# ATMEGA128RF.net
KiCad netlist of a schematic drawn in Altium Designer
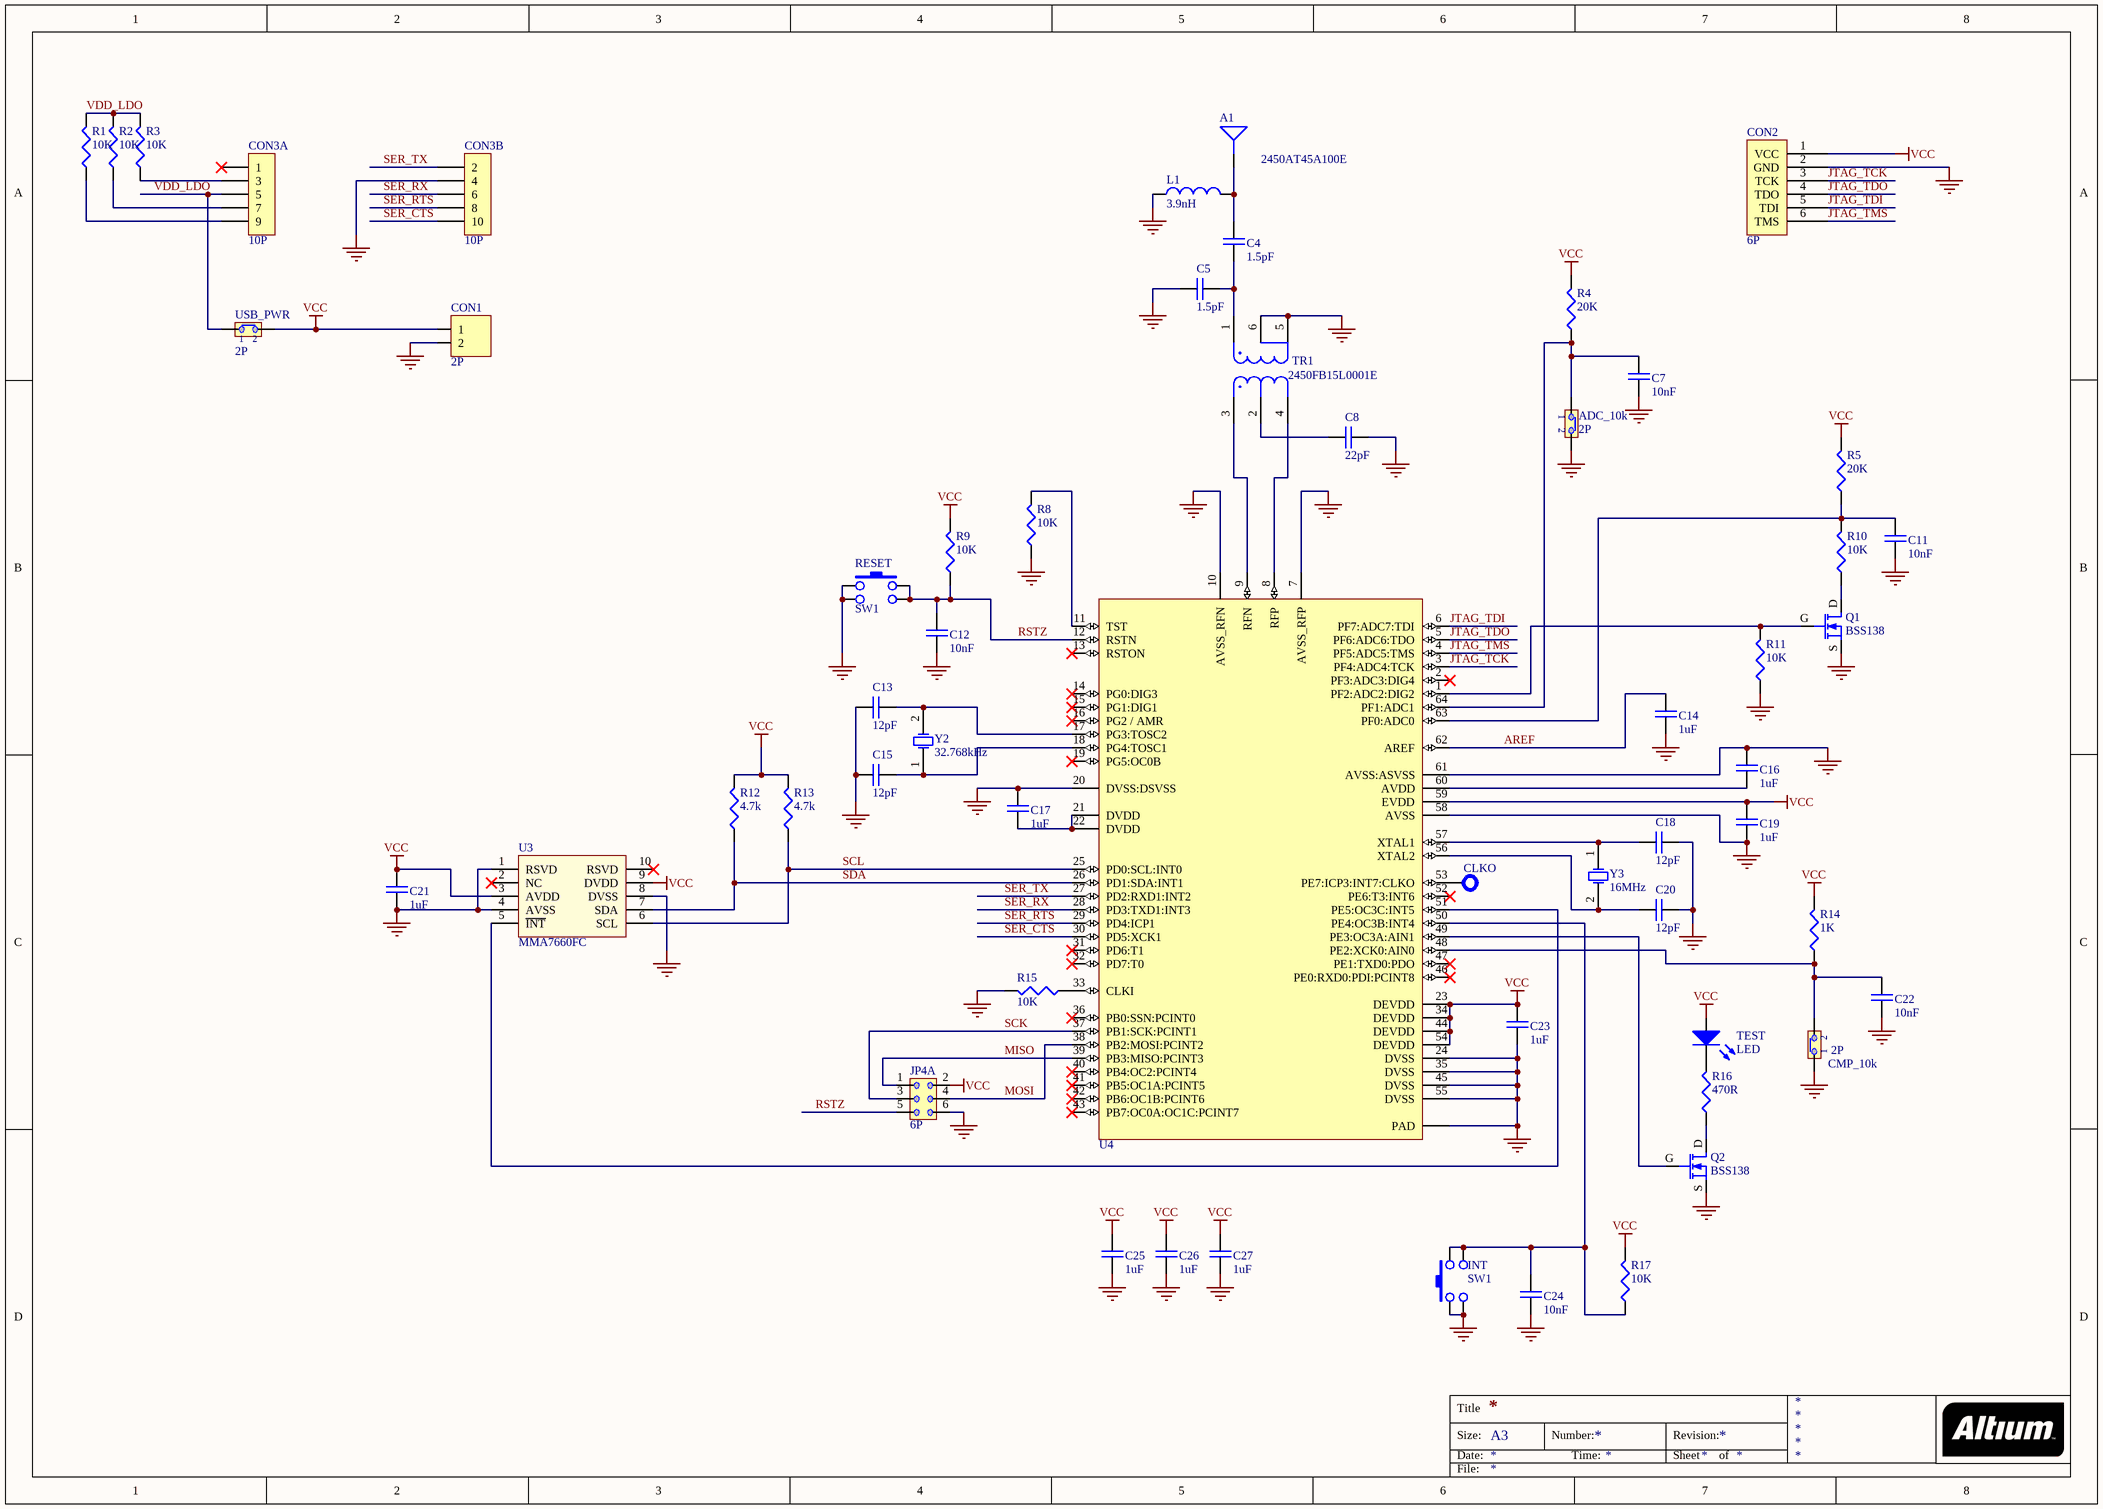
[diagram p0: ATMEGA128RF.SchDoc]

(export (version "E")
  (design (tool "Eeschema 10.0.6"))
  (components
    (comp (ref "A1")
      (value "2450AT45A100E")
      (footprint "2450AT45A100E")
      (description "ANTENNA")
      (libsource (lib "Alcetronics_Devices") (part "Antenna SE"))
    )
    (comp (ref "ADC_10k")
      (value "2P")
      (footprint "SIP-2")
      (description "2-pin Jumper")
      (fields (field (name "OWNER") "Nuno Brum"))
      (libsource (lib "Alcetronics_EM") (part "JMP2"))
    )
    (comp (ref "C4")
      (value "1.5pF")
      (footprint "0402")
      (description "Capacitor")
      (fields (field (name "OWNER") "Nuno Brum"))
      (libsource (lib "Alcetronics_Devices") (part "CAP"))
    )
    (comp (ref "C5")
      (value "1.5pF")
      (footprint "0402")
      (description "Capacitor")
      (fields (field (name "OWNER") "Nuno Brum"))
      (libsource (lib "Alcetronics_Devices") (part "CAP"))
    )
    (comp (ref "C7")
      (value "10nF")
      (footprint "0603")
      (description "Capacitor")
      (fields (field (name "OWNER") "Nuno Brum"))
      (libsource (lib "Alcetronics_Devices") (part "CAP"))
    )
    (comp (ref "C8")
      (value "22pF")
      (footprint "0402")
      (description "Capacitor")
      (fields (field (name "OWNER") "Nuno Brum"))
      (libsource (lib "Alcetronics_Devices") (part "CAP"))
    )
    (comp (ref "C11")
      (value "10nF")
      (footprint "0603")
      (description "Capacitor")
      (fields (field (name "OWNER") "Nuno Brum"))
      (libsource (lib "Alcetronics_Devices") (part "CAP"))
    )
    (comp (ref "C12")
      (value "10nF")
      (footprint "0603")
      (description "Capacitor")
      (fields (field (name "OWNER") "Nuno Brum"))
      (libsource (lib "Alcetronics_Devices") (part "CAP"))
    )
    (comp (ref "C13")
      (value "12pF")
      (footprint "0603")
      (description "Capacitor")
      (fields (field (name "OWNER") "Nuno Brum"))
      (libsource (lib "Alcetronics_Devices") (part "CAP"))
    )
    (comp (ref "C14")
      (value "1uF")
      (footprint "0603")
      (description "Capacitor")
      (fields (field (name "OWNER") "Nuno Brum"))
      (libsource (lib "Alcetronics_Devices") (part "CAP"))
    )
    (comp (ref "C15")
      (value "12pF")
      (footprint "0603")
      (description "Capacitor")
      (fields (field (name "OWNER") "Nuno Brum"))
      (libsource (lib "Alcetronics_Devices") (part "CAP"))
    )
    (comp (ref "C16")
      (value "1uF")
      (footprint "0603")
      (description "Capacitor")
      (fields (field (name "OWNER") "Nuno Brum"))
      (libsource (lib "Alcetronics_Devices") (part "CAP"))
    )
    (comp (ref "C17")
      (value "1uF")
      (footprint "0603")
      (description "Capacitor")
      (fields (field (name "OWNER") "Nuno Brum"))
      (libsource (lib "Alcetronics_Devices") (part "CAP"))
    )
    (comp (ref "C18")
      (value "12pF")
      (footprint "0603")
      (description "Capacitor")
      (fields (field (name "OWNER") "Nuno Brum"))
      (libsource (lib "Alcetronics_Devices") (part "CAP"))
    )
    (comp (ref "C19")
      (value "1uF")
      (footprint "0603")
      (description "Capacitor")
      (fields (field (name "OWNER") "Nuno Brum"))
      (libsource (lib "Alcetronics_Devices") (part "CAP"))
    )
    (comp (ref "C20")
      (value "12pF")
      (footprint "0603")
      (description "Capacitor")
      (fields (field (name "OWNER") "Nuno Brum"))
      (libsource (lib "Alcetronics_Devices") (part "CAP"))
    )
    (comp (ref "C21")
      (value "1uF")
      (footprint "0603")
      (description "Capacitor")
      (fields (field (name "OWNER") "Nuno Brum"))
      (libsource (lib "Alcetronics_Devices") (part "CAP"))
    )
    (comp (ref "C22")
      (value "10nF")
      (footprint "0603")
      (description "Capacitor")
      (fields (field (name "OWNER") "Nuno Brum"))
      (libsource (lib "Alcetronics_Devices") (part "CAP"))
    )
    (comp (ref "C23")
      (value "1uF")
      (footprint "0603")
      (description "Capacitor")
      (fields (field (name "OWNER") "Nuno Brum"))
      (libsource (lib "Alcetronics_Devices") (part "CAP"))
    )
    (comp (ref "C24")
      (value "10nF")
      (footprint "0603")
      (description "Capacitor")
      (fields (field (name "OWNER") "Nuno Brum"))
      (libsource (lib "Alcetronics_Devices") (part "CAP"))
    )
    (comp (ref "C25")
      (value "1uF")
      (footprint "0603")
      (description "Capacitor")
      (fields (field (name "OWNER") "Nuno Brum"))
      (libsource (lib "Alcetronics_Devices") (part "CAP"))
    )
    (comp (ref "C26")
      (value "1uF")
      (footprint "0603")
      (description "Capacitor")
      (fields (field (name "OWNER") "Nuno Brum"))
      (libsource (lib "Alcetronics_Devices") (part "CAP"))
    )
    (comp (ref "C27")
      (value "1uF")
      (footprint "0603")
      (description "Capacitor")
      (fields (field (name "OWNER") "Nuno Brum"))
      (libsource (lib "Alcetronics_Devices") (part "CAP"))
    )
    (comp (ref "CLKO")
      (value "Test Point")
      (footprint "TERMINAL")
      (description "Test/Probe Point")
      (fields (field (name "OWNER") "Nuno Brum"))
      (libsource (lib "Alcetronics_EM") (part "TEST-PROBE"))
    )
    (comp (ref "CMP_10k")
      (value "2P")
      (footprint "SIP-2")
      (description "2-pin Jumper")
      (fields (field (name "OWNER") "Nuno Brum"))
      (libsource (lib "") (part "JMP2_1"))
    )
    (comp (ref "CON1")
      (value "2P")
      (footprint "INTERLOCK2-5MM")
      (description "Connector 2 pins")
      (fields (field (name "OWNER") "Rui Rebelo"))
      (libsource (lib "Alcetronics_EM") (part "CON02"))
    )
    (comp (ref "CON2")
      (value "6P")
      (footprint "SIP-6-JTAG")
      (description "Generic JTAG Connector")
      (fields (field (name "OWNER") "António Oliveira"))
      (libsource (lib "Alcetronics_EM") (part "CON-JTAG"))
    )
    (comp (ref "CON3")
      (value "10P")
      (footprint "IDC-10-90")
      (description "Connector 10 Pins")
      (fields (field (name "OWNER") "António Silva"))
      (libsource (lib "Alcetronics_EM") (part "CON10"))
    )
    (comp (ref "INT")
      (value "SW1")
      (footprint "MICROSWITCH")
      (description "Switch Push Button")
      (fields (field (name "OWNER") "Nuno Brum"))
      (libsource (lib "Alcetronics_EM") (part "SW1"))
    )
    (comp (ref "JP4")
      (value "6P")
      (footprint "DIL-6")
      (description "6-Pin Jumper")
      (fields (field (name "OWNER") "Rui Rebelo"))
      (libsource (lib "Alcetronics_EM") (part "JMP6"))
    )
    (comp (ref "L1")
      (value "3.9nH")
      (footprint "0402")
      (description "Inductor")
      (fields (field (name "OWNER") "Nuno Brum"))
      (libsource (lib "Alcetronics_Devices") (part "IND"))
    )
    (comp (ref "Q1")
      (value "BSS138")
      (footprint "SOT-23@GSD")
      (description "N-Channel Logic Level Enhancement Mode Field Effect Transistor")
      (fields (field (name "OWNER") "Nuno Brum"))
      (libsource (lib "Alcetronics_Devices") (part "MOSFET-N"))
    )
    (comp (ref "Q2")
      (value "BSS138")
      (footprint "SOT-23@GSD")
      (description "N-Channel Logic Level Enhancement Mode Field Effect Transistor")
      (fields (field (name "OWNER") "Nuno Brum"))
      (libsource (lib "Alcetronics_Devices") (part "MOSFET-N"))
    )
    (comp (ref "R1")
      (value "10K")
      (footprint "0603")
      (description "Resistor")
      (fields (field (name "OWNER") "Nuno Brum"))
      (libsource (lib "Alcetronics_Devices") (part "RES"))
    )
    (comp (ref "R2")
      (value "10K")
      (footprint "0603")
      (description "Resistor")
      (fields (field (name "OWNER") "Nuno Brum"))
      (libsource (lib "Alcetronics_Devices") (part "RES"))
    )
    (comp (ref "R3")
      (value "10K")
      (footprint "0603")
      (description "Resistor")
      (fields (field (name "OWNER") "Nuno Brum"))
      (libsource (lib "Alcetronics_Devices") (part "RES"))
    )
    (comp (ref "R4")
      (value "20K")
      (footprint "0603")
      (description "Resistor")
      (fields (field (name "OWNER") "Nuno Brum"))
      (libsource (lib "Alcetronics_Devices") (part "RES"))
    )
    (comp (ref "R5")
      (value "20K")
      (footprint "0603")
      (description "Resistor")
      (fields (field (name "OWNER") "Nuno Brum"))
      (libsource (lib "Alcetronics_Devices") (part "RES"))
    )
    (comp (ref "R8")
      (value "10K")
      (footprint "0603")
      (description "Resistor")
      (fields (field (name "OWNER") "Nuno Brum"))
      (libsource (lib "Alcetronics_Devices") (part "RES"))
    )
    (comp (ref "R9")
      (value "10K")
      (footprint "0603")
      (description "Resistor")
      (fields (field (name "OWNER") "Nuno Brum"))
      (libsource (lib "Alcetronics_Devices") (part "RES"))
    )
    (comp (ref "R10")
      (value "10K")
      (footprint "0603")
      (description "Resistor")
      (fields (field (name "OWNER") "Nuno Brum"))
      (libsource (lib "Alcetronics_Devices") (part "RES"))
    )
    (comp (ref "R11")
      (value "10K")
      (footprint "0603")
      (description "Resistor")
      (fields (field (name "OWNER") "Nuno Brum"))
      (libsource (lib "Alcetronics_Devices") (part "RES"))
    )
    (comp (ref "R12")
      (value "4.7k")
      (footprint "0603")
      (description "Resistor")
      (fields (field (name "OWNER") "Nuno Brum"))
      (libsource (lib "Alcetronics_Devices") (part "RES"))
    )
    (comp (ref "R13")
      (value "4.7k")
      (footprint "0603")
      (description "Resistor")
      (fields (field (name "OWNER") "Nuno Brum"))
      (libsource (lib "Alcetronics_Devices") (part "RES"))
    )
    (comp (ref "R14")
      (value "1K")
      (footprint "0603")
      (description "Resistor")
      (fields (field (name "OWNER") "Nuno Brum"))
      (libsource (lib "Alcetronics_Devices") (part "RES"))
    )
    (comp (ref "R15")
      (value "10K")
      (footprint "0603")
      (description "Resistor")
      (fields (field (name "OWNER") "Nuno Brum"))
      (libsource (lib "Alcetronics_Devices") (part "RES"))
    )
    (comp (ref "R16")
      (value "470R")
      (footprint "0603")
      (description "Resistor")
      (fields (field (name "OWNER") "Nuno Brum"))
      (libsource (lib "Alcetronics_Devices") (part "RES"))
    )
    (comp (ref "R17")
      (value "10K")
      (footprint "0603")
      (description "Resistor")
      (fields (field (name "OWNER") "Nuno Brum"))
      (libsource (lib "Alcetronics_Devices") (part "RES"))
    )
    (comp (ref "RESET")
      (value "SW1")
      (footprint "MICROSWITCH")
      (description "Switch Push Button")
      (fields (field (name "OWNER") "Nuno Brum"))
      (libsource (lib "Alcetronics_EM") (part "SW1"))
    )
    (comp (ref "TEST")
      (value "LED")
      (footprint "0805@DIODE")
      (description "Light emitting diode")
      (fields (field (name "OWNER") "Nuno Brum"))
      (libsource (lib "Alcetronics_Devices") (part "LED"))
    )
    (comp (ref "TR1")
      (value "2450FB15L0001E")
      (footprint "0805@BALUN")
      (description "FILTER BALUN ATMEL 2.45GHZ")
      (fields (field (name "OWNER") "Rui Rebelo"))
      (libsource (lib "Alcetronics_Devices") (part "2450FB15L0001E"))
    )
    (comp (ref "U3")
      (value "MMA7660FC")
      (footprint "DFN-10")
      (description "3-Axis Orientation/Motion Detection Sensor")
      (libsource (lib "Alcetronics_IC") (part "MMA7660FC"))
    )
    (comp (ref "U4")
      (value "ATmega128RFA1")
      (footprint "QFN-64@EP")
      (description "802.15.4 compliant AVR transceiver")
      (fields (field (name "VERIFIED BY") "vlarsen"))
      (libsource (lib "Alcetronics_IC") (part "ATmega128RFA1"))
    )
    (comp (ref "USB_PWR")
      (value "2P")
      (footprint "SIP-2")
      (description "2-pin Jumper")
      (fields (field (name "OWNER") "Nuno Brum"))
      (libsource (lib "") (part "JMP2_2"))
    )
    (comp (ref "Y2")
      (value "32.768kHz")
      (footprint "HC-49U")
      (description "Crystal Oscillator")
      (fields (field (name "PUBLISHER") "Altium Limited"))
      (libsource (lib "Alcetronics_Devices") (part "Crystal Oscillator"))
    )
    (comp (ref "Y3")
      (value "16MHz")
      (footprint "HC-49U")
      (description "Crystal Oscillator")
      (fields (field (name "PUBLISHER") "Altium Limited"))
      (libsource (lib "Alcetronics_Devices") (part "Crystal Oscillator"))
    )
  )
  (nets
    (net (code "1") (name "/AREF") (class "Default")
      (node (ref "C14") (pin "2") (pinfunction "2_2") (pintype "passive"))
      (node (ref "U4") (pin "62") (pinfunction "AREF_62") (pintype "bidirectional"))
    )
    (net (code "2") (name "/JTAG_TCK") (class "Default")
      (node (ref "CON2") (pin "3") (pinfunction "TCK_3") (pintype "passive"))
      (node (ref "U4") (pin "3") (pinfunction "PF4:ADC4:TCK_3") (pintype "bidirectional"))
    )
    (net (code "3") (name "/JTAG_TDI") (class "Default")
      (node (ref "CON2") (pin "5") (pinfunction "TDI_5") (pintype "passive"))
      (node (ref "U4") (pin "6") (pinfunction "PF7:ADC7:TDI_6") (pintype "bidirectional"))
    )
    (net (code "4") (name "/JTAG_TDO") (class "Default")
      (node (ref "CON2") (pin "4") (pinfunction "TDO_4") (pintype "passive"))
      (node (ref "U4") (pin "5") (pinfunction "PF6:ADC6:TDO_5") (pintype "bidirectional"))
    )
    (net (code "5") (name "/JTAG_TMS") (class "Default")
      (node (ref "CON2") (pin "6") (pinfunction "TMS_6") (pintype "passive"))
      (node (ref "U4") (pin "4") (pinfunction "PF5:ADC5:TMS_4") (pintype "bidirectional"))
    )
    (net (code "6") (name "/MISO") (class "Default")
      (node (ref "JP4") (pin "1") (pinfunction "1_1") (pintype "passive"))
      (node (ref "U4") (pin "39") (pinfunction "PB3:MISO:PCINT3_39") (pintype "bidirectional"))
    )
    (net (code "7") (name "/MOSI") (class "Default")
      (node (ref "JP4") (pin "4") (pinfunction "4_4") (pintype "passive"))
      (node (ref "U4") (pin "38") (pinfunction "PB2:MOSI:PCINT2_38") (pintype "bidirectional"))
    )
    (net (code "8") (name "/RSTZ") (class "Default")
      (node (ref "C12") (pin "1") (pinfunction "1_1") (pintype "passive"))
      (node (ref "JP4") (pin "5") (pinfunction "5_5") (pintype "passive"))
      (node (ref "R9") (pin "1") (pinfunction "1_1") (pintype "passive"))
      (node (ref "RESET") (pin "2") (pinfunction "2_2") (pintype "passive"))
      (node (ref "RESET") (pin "4") (pinfunction "4_4") (pintype "passive"))
      (node (ref "U4") (pin "12") (pinfunction "RSTN_12") (pintype "bidirectional"))
    )
    (net (code "9") (name "/SCK") (class "Default")
      (node (ref "JP4") (pin "3") (pinfunction "3_3") (pintype "passive"))
      (node (ref "U4") (pin "37") (pinfunction "PB1:SCK:PCINT1_37") (pintype "bidirectional"))
    )
    (net (code "10") (name "/SCL") (class "Default")
      (node (ref "R13") (pin "1") (pinfunction "1_1") (pintype "passive"))
      (node (ref "U3") (pin "6") (pinfunction "SCL_6") (pintype "passive"))
      (node (ref "U4") (pin "25") (pinfunction "PD0:SCL:INT0_25") (pintype "bidirectional"))
    )
    (net (code "11") (name "/SDA") (class "Default")
      (node (ref "R12") (pin "1") (pinfunction "1_1") (pintype "passive"))
      (node (ref "U3") (pin "7") (pinfunction "SDA_7") (pintype "passive"))
      (node (ref "U4") (pin "26") (pinfunction "PD1:SDA:INT1_26") (pintype "bidirectional"))
    )
    (net (code "12") (name "/SER_CTS") (class "Default")
      (node (ref "CON3") (pin "10") (pinfunction "10_10") (pintype "passive"))
      (node (ref "U4") (pin "30") (pinfunction "PD5:XCK1_30") (pintype "bidirectional"))
    )
    (net (code "13") (name "/SER_RTS") (class "Default")
      (node (ref "CON3") (pin "8") (pinfunction "8_8") (pintype "passive"))
      (node (ref "U4") (pin "29") (pinfunction "PD4:ICP1_29") (pintype "bidirectional"))
    )
    (net (code "14") (name "/SER_RX") (class "Default")
      (node (ref "CON3") (pin "6") (pinfunction "6_6") (pintype "passive"))
      (node (ref "U4") (pin "28") (pinfunction "PD3:TXD1:INT3_28") (pintype "bidirectional"))
    )
    (net (code "15") (name "/SER_TX") (class "Default")
      (node (ref "CON3") (pin "2") (pinfunction "2_2") (pintype "passive"))
      (node (ref "U4") (pin "27") (pinfunction "PD2:RXD1:INT2_27") (pintype "bidirectional"))
    )
    (net (code "16") (name "/VDD_LDO") (class "Default")
      (node (ref "CON3") (pin "5") (pinfunction "5_5") (pintype "passive"))
      (node (ref "R1") (pin "2") (pinfunction "2_2") (pintype "passive"))
      (node (ref "R2") (pin "2") (pinfunction "2_2") (pintype "passive"))
      (node (ref "R3") (pin "2") (pinfunction "2_2") (pintype "passive"))
      (node (ref "USB_PWR") (pin "1") (pinfunction "1_1") (pintype "passive"))
    )
    (net (code "17") (name "GND") (class "Default")
      (node (ref "ADC_10k") (pin "2") (pinfunction "2_2") (pintype "passive"))
      (node (ref "C11") (pin "1") (pinfunction "1_1") (pintype "passive"))
      (node (ref "C12") (pin "2") (pinfunction "2_2") (pintype "passive"))
      (node (ref "C13") (pin "1") (pinfunction "1_1") (pintype "passive"))
      (node (ref "C14") (pin "1") (pinfunction "1_1") (pintype "passive"))
      (node (ref "C15") (pin "1") (pinfunction "1_1") (pintype "passive"))
      (node (ref "C16") (pin "2") (pinfunction "2_2") (pintype "passive"))
      (node (ref "C17") (pin "2") (pinfunction "2_2") (pintype "passive"))
      (node (ref "C18") (pin "2") (pinfunction "2_2") (pintype "passive"))
      (node (ref "C19") (pin "1") (pinfunction "1_1") (pintype "passive"))
      (node (ref "C20") (pin "2") (pinfunction "2_2") (pintype "passive"))
      (node (ref "C21") (pin "1") (pinfunction "1_1") (pintype "passive"))
      (node (ref "C22") (pin "1") (pinfunction "1_1") (pintype "passive"))
      (node (ref "C23") (pin "1") (pinfunction "1_1") (pintype "passive"))
      (node (ref "C24") (pin "1") (pinfunction "1_1") (pintype "passive"))
      (node (ref "C25") (pin "1") (pinfunction "1_1") (pintype "passive"))
      (node (ref "C26") (pin "1") (pinfunction "1_1") (pintype "passive"))
      (node (ref "C27") (pin "1") (pinfunction "1_1") (pintype "passive"))
      (node (ref "C5") (pin "1") (pinfunction "1_1") (pintype "passive"))
      (node (ref "C7") (pin "2") (pinfunction "2_2") (pintype "passive"))
      (node (ref "C8") (pin "2") (pinfunction "2_2") (pintype "passive"))
      (node (ref "CMP_10k") (pin "1") (pinfunction "1_1") (pintype "passive"))
      (node (ref "CON1") (pin "2") (pinfunction "2_2") (pintype "passive"))
      (node (ref "CON2") (pin "2") (pinfunction "GND_2") (pintype "passive"))
      (node (ref "CON3") (pin "4") (pinfunction "4_4") (pintype "passive"))
      (node (ref "INT") (pin "2") (pinfunction "2_2") (pintype "passive"))
      (node (ref "INT") (pin "4") (pinfunction "4_4") (pintype "passive"))
      (node (ref "JP4") (pin "6") (pinfunction "6_6") (pintype "passive"))
      (node (ref "L1") (pin "1") (pinfunction "1_1") (pintype "passive"))
      (node (ref "Q1") (pin "S") (pinfunction "S_S") (pintype "passive"))
      (node (ref "Q2") (pin "S") (pinfunction "S_S") (pintype "passive"))
      (node (ref "R11") (pin "1") (pinfunction "1_1") (pintype "passive"))
      (node (ref "R15") (pin "2") (pinfunction "2_2") (pintype "passive"))
      (node (ref "R8") (pin "1") (pinfunction "1_1") (pintype "passive"))
      (node (ref "RESET") (pin "1") (pinfunction "1_1") (pintype "passive"))
      (node (ref "RESET") (pin "3") (pinfunction "3_3") (pintype "passive"))
      (node (ref "TR1") (pin "5") (pinfunction "Ground_5") (pintype "passive"))
      (node (ref "TR1") (pin "6") (pinfunction "Ground_6") (pintype "passive"))
      (node (ref "U3") (pin "1") (pinfunction "RSVD_1") (pintype "passive"))
      (node (ref "U3") (pin "4") (pinfunction "AVSS_4") (pintype "passive"))
      (node (ref "U3") (pin "8") (pinfunction "DVSS_8") (pintype "passive"))
      (node (ref "U4") (pin "10") (pinfunction "AVSS_RFN_10") (pintype "power_in"))
      (node (ref "U4") (pin "20") (pinfunction "DVSS:DSVSS_20") (pintype "power_in"))
      (node (ref "U4") (pin "24") (pinfunction "DVSS_24") (pintype "power_in"))
      (node (ref "U4") (pin "35") (pinfunction "DVSS_35") (pintype "power_in"))
      (node (ref "U4") (pin "45") (pinfunction "DVSS_45") (pintype "power_in"))
      (node (ref "U4") (pin "55") (pinfunction "DVSS_55") (pintype "power_in"))
      (node (ref "U4") (pin "58") (pinfunction "AVSS_58") (pintype "power_in"))
      (node (ref "U4") (pin "61") (pinfunction "AVSS:ASVSS_61") (pintype "power_in"))
      (node (ref "U4") (pin "7") (pinfunction "AVSS_RFP_7") (pintype "power_in"))
      (node (ref "U4") (pin "PAD") (pinfunction "PAD_PAD") (pintype "power_in"))
    )
    (net (code "18") (name "Net-(A1-Pad1)") (class "Default")
      (node (ref "A1") (pin "1") (pinfunction "1_1") (pintype "passive"))
      (node (ref "C4") (pin "2") (pinfunction "2_2") (pintype "passive"))
      (node (ref "L1") (pin "2") (pinfunction "2_2") (pintype "passive"))
    )
    (net (code "19") (name "Net-(C17-Pad1)") (class "Default")
      (node (ref "C17") (pin "1") (pinfunction "1_1") (pintype "passive"))
      (node (ref "U4") (pin "21") (pinfunction "DVDD_21") (pintype "power_in"))
      (node (ref "U4") (pin "22") (pinfunction "DVDD_22") (pintype "power_in"))
    )
    (net (code "20") (name "Net-(CLKO-TP)") (class "Default")
      (node (ref "CLKO") (pin "1") (pinfunction "TP_1") (pintype "passive"))
      (node (ref "U4") (pin "53") (pinfunction "PE7:ICP3:INT7:CLKO_53") (pintype "bidirectional"))
    )
    (net (code "21") (name "Net-(CON3-Pad3)") (class "Default")
      (node (ref "CON3") (pin "3") (pinfunction "3_3") (pintype "passive"))
      (node (ref "R3") (pin "1") (pinfunction "1_1") (pintype "passive"))
    )
    (net (code "22") (name "Net-(CON3-Pad7)") (class "Default")
      (node (ref "CON3") (pin "7") (pinfunction "7_7") (pintype "passive"))
      (node (ref "R2") (pin "1") (pinfunction "1_1") (pintype "passive"))
    )
    (net (code "23") (name "Net-(CON3-Pad9)") (class "Default")
      (node (ref "CON3") (pin "9") (pinfunction "9_9") (pintype "passive"))
      (node (ref "R1") (pin "1") (pinfunction "1_1") (pintype "passive"))
    )
    (net (code "24") (name "Net-(Q1-PadD)") (class "Default")
      (node (ref "Q1") (pin "D") (pinfunction "D_D") (pintype "passive"))
      (node (ref "R10") (pin "1") (pinfunction "1_1") (pintype "passive"))
    )
    (net (code "25") (name "Net-(Q2-PadD)") (class "Default")
      (node (ref "Q2") (pin "D") (pinfunction "D_D") (pintype "passive"))
      (node (ref "R16") (pin "1") (pinfunction "1_1") (pintype "passive"))
    )
    (net (code "26") (name "Net-(R16-Pad2)") (class "Default")
      (node (ref "R16") (pin "2") (pinfunction "2_2") (pintype "passive"))
      (node (ref "TEST") (pin "K") (pinfunction "K_K") (pintype "passive"))
    )
    (net (code "27") (name "Net-(TR1-DC_Feed_+_RF_GND)") (class "Default")
      (node (ref "C8") (pin "1") (pinfunction "1_1") (pintype "passive"))
      (node (ref "TR1") (pin "2") (pinfunction "DC_Feed_+_RF_GND_2") (pintype "passive"))
    )
    (net (code "28") (name "Net-(TR1-Unbalanced_Port)") (class "Default")
      (node (ref "C4") (pin "1") (pinfunction "1_1") (pintype "passive"))
      (node (ref "C5") (pin "2") (pinfunction "2_2") (pintype "passive"))
      (node (ref "TR1") (pin "1") (pinfunction "Unbalanced_Port_1") (pintype "passive"))
    )
    (net (code "29") (name "Net-(U3-~{INT})") (class "Default")
      (node (ref "U3") (pin "5") (pinfunction "~{INT}_5") (pintype "passive"))
      (node (ref "U4") (pin "51") (pinfunction "PE5:OC3C:INT5_51") (pintype "bidirectional"))
    )
    (net (code "30") (name "Net-(U4-AVDD)") (class "Default")
      (node (ref "C16") (pin "1") (pinfunction "1_1") (pintype "passive"))
      (node (ref "U4") (pin "60") (pinfunction "AVDD_60") (pintype "power_in"))
    )
    (net (code "31") (name "Net-(U4-CLKI)") (class "Default")
      (node (ref "R15") (pin "1") (pinfunction "1_1") (pintype "passive"))
      (node (ref "U4") (pin "33") (pinfunction "CLKI_33") (pintype "bidirectional"))
    )
    (net (code "32") (name "Net-(U4-PE2:XCK0:AIN0)") (class "Default")
      (node (ref "C22") (pin "2") (pinfunction "2_2") (pintype "passive"))
      (node (ref "CMP_10k") (pin "2") (pinfunction "2_2") (pintype "passive"))
      (node (ref "R14") (pin "1") (pinfunction "1_1") (pintype "passive"))
      (node (ref "U4") (pin "48") (pinfunction "PE2:XCK0:AIN0_48") (pintype "bidirectional"))
    )
    (net (code "33") (name "Net-(U4-PE3:OC3A:AIN1)") (class "Default")
      (node (ref "Q2") (pin "G") (pinfunction "G_G") (pintype "passive"))
      (node (ref "U4") (pin "49") (pinfunction "PE3:OC3A:AIN1_49") (pintype "bidirectional"))
    )
    (net (code "34") (name "Net-(U4-PE4:OC3B:INT4)") (class "Default")
      (node (ref "C24") (pin "2") (pinfunction "2_2") (pintype "passive"))
      (node (ref "INT") (pin "1") (pinfunction "1_1") (pintype "passive"))
      (node (ref "INT") (pin "3") (pinfunction "3_3") (pintype "passive"))
      (node (ref "R17") (pin "1") (pinfunction "1_1") (pintype "passive"))
      (node (ref "U4") (pin "50") (pinfunction "PE4:OC3B:INT4_50") (pintype "bidirectional"))
    )
    (net (code "35") (name "Net-(U4-PF0:ADC0)") (class "Default")
      (node (ref "C11") (pin "2") (pinfunction "2_2") (pintype "passive"))
      (node (ref "R10") (pin "2") (pinfunction "2_2") (pintype "passive"))
      (node (ref "R5") (pin "1") (pinfunction "1_1") (pintype "passive"))
      (node (ref "U4") (pin "63") (pinfunction "PF0:ADC0_63") (pintype "bidirectional"))
    )
    (net (code "36") (name "Net-(U4-PF1:ADC1)") (class "Default")
      (node (ref "ADC_10k") (pin "1") (pinfunction "1_1") (pintype "passive"))
      (node (ref "C7") (pin "1") (pinfunction "1_1") (pintype "passive"))
      (node (ref "R4") (pin "1") (pinfunction "1_1") (pintype "passive"))
      (node (ref "U4") (pin "64") (pinfunction "PF1:ADC1_64") (pintype "bidirectional"))
    )
    (net (code "37") (name "Net-(U4-PF2:ADC2:DIG2)") (class "Default")
      (node (ref "Q1") (pin "G") (pinfunction "G_G") (pintype "passive"))
      (node (ref "R11") (pin "2") (pinfunction "2_2") (pintype "passive"))
      (node (ref "U4") (pin "1") (pinfunction "PF2:ADC2:DIG2_1") (pintype "bidirectional"))
    )
    (net (code "38") (name "Net-(U4-PG3:TOSC2)") (class "Default")
      (node (ref "C13") (pin "2") (pinfunction "2_2") (pintype "passive"))
      (node (ref "U4") (pin "17") (pinfunction "PG3:TOSC2_17") (pintype "bidirectional"))
      (node (ref "Y2") (pin "2") (pinfunction "OSC2_2") (pintype "passive"))
    )
    (net (code "39") (name "Net-(U4-PG4:TOSC1)") (class "Default")
      (node (ref "C15") (pin "2") (pinfunction "2_2") (pintype "passive"))
      (node (ref "U4") (pin "18") (pinfunction "PG4:TOSC1_18") (pintype "bidirectional"))
      (node (ref "Y2") (pin "1") (pinfunction "OSC1_1") (pintype "passive"))
    )
    (net (code "40") (name "Net-(U4-RFN)") (class "Default")
      (node (ref "TR1") (pin "3") (pinfunction "Balanced_Port_3") (pintype "passive"))
      (node (ref "U4") (pin "9") (pinfunction "RFN_9") (pintype "bidirectional"))
    )
    (net (code "41") (name "Net-(U4-RFP)") (class "Default")
      (node (ref "TR1") (pin "4") (pinfunction "Balanced_Port_4") (pintype "passive"))
      (node (ref "U4") (pin "8") (pinfunction "RFP_8") (pintype "bidirectional"))
    )
    (net (code "42") (name "Net-(U4-TST)") (class "Default")
      (node (ref "R8") (pin "2") (pinfunction "2_2") (pintype "passive"))
      (node (ref "U4") (pin "11") (pinfunction "TST_11") (pintype "bidirectional"))
    )
    (net (code "43") (name "Net-(U4-XTAL1)") (class "Default")
      (node (ref "C18") (pin "1") (pinfunction "1_1") (pintype "passive"))
      (node (ref "U4") (pin "57") (pinfunction "XTAL1_57") (pintype "bidirectional"))
      (node (ref "Y3") (pin "1") (pinfunction "OSC1_1") (pintype "passive"))
    )
    (net (code "44") (name "Net-(U4-XTAL2)") (class "Default")
      (node (ref "C20") (pin "1") (pinfunction "1_1") (pintype "passive"))
      (node (ref "U4") (pin "56") (pinfunction "XTAL2_56") (pintype "bidirectional"))
      (node (ref "Y3") (pin "2") (pinfunction "OSC2_2") (pintype "passive"))
    )
    (net (code "45") (name "VCC") (class "Default")
      (node (ref "C19") (pin "2") (pinfunction "2_2") (pintype "passive"))
      (node (ref "C21") (pin "2") (pinfunction "2_2") (pintype "passive"))
      (node (ref "C23") (pin "2") (pinfunction "2_2") (pintype "passive"))
      (node (ref "C25") (pin "2") (pinfunction "2_2") (pintype "passive"))
      (node (ref "C26") (pin "2") (pinfunction "2_2") (pintype "passive"))
      (node (ref "C27") (pin "2") (pinfunction "2_2") (pintype "passive"))
      (node (ref "CON1") (pin "1") (pinfunction "1_1") (pintype "passive"))
      (node (ref "CON2") (pin "1") (pinfunction "VCC_1") (pintype "passive"))
      (node (ref "JP4") (pin "2") (pinfunction "2_2") (pintype "passive"))
      (node (ref "R12") (pin "2") (pinfunction "2_2") (pintype "passive"))
      (node (ref "R13") (pin "2") (pinfunction "2_2") (pintype "passive"))
      (node (ref "R14") (pin "2") (pinfunction "2_2") (pintype "passive"))
      (node (ref "R17") (pin "2") (pinfunction "2_2") (pintype "passive"))
      (node (ref "R4") (pin "2") (pinfunction "2_2") (pintype "passive"))
      (node (ref "R5") (pin "2") (pinfunction "2_2") (pintype "passive"))
      (node (ref "R9") (pin "2") (pinfunction "2_2") (pintype "passive"))
      (node (ref "TEST") (pin "A") (pinfunction "A_A") (pintype "passive"))
      (node (ref "U3") (pin "3") (pinfunction "AVDD_3") (pintype "passive"))
      (node (ref "U3") (pin "9") (pinfunction "DVDD_9") (pintype "passive"))
      (node (ref "U4") (pin "23") (pinfunction "DEVDD_23") (pintype "power_in"))
      (node (ref "U4") (pin "34") (pinfunction "DEVDD_34") (pintype "power_in"))
      (node (ref "U4") (pin "44") (pinfunction "DEVDD_44") (pintype "power_in"))
      (node (ref "U4") (pin "54") (pinfunction "DEVDD_54") (pintype "power_in"))
      (node (ref "U4") (pin "59") (pinfunction "EVDD_59") (pintype "power_in"))
      (node (ref "USB_PWR") (pin "2") (pinfunction "2_2") (pintype "passive"))
    )
    (net (code "46") (name "unconnected-(CON3-Pad1)") (class "Default")
      (node (ref "CON3") (pin "1") (pinfunction "1_1") (pintype "passive+no_connect"))
    )
    (net (code "47") (name "unconnected-(U3-NC-Pad2)") (class "Default")
      (node (ref "U3") (pin "2") (pinfunction "NC_2") (pintype "passive+no_connect"))
    )
    (net (code "48") (name "unconnected-(U3-RSVD-Pad10)") (class "Default")
      (node (ref "U3") (pin "10") (pinfunction "RSVD_10") (pintype "passive+no_connect"))
    )
    (net (code "49") (name "unconnected-(U4-PB0:SSN:PCINT0-Pad36)") (class "Default")
      (node (ref "U4") (pin "36") (pinfunction "PB0:SSN:PCINT0_36") (pintype "bidirectional+no_connect"))
    )
    (net (code "50") (name "unconnected-(U4-PB4:OC2:PCINT4-Pad40)") (class "Default")
      (node (ref "U4") (pin "40") (pinfunction "PB4:OC2:PCINT4_40") (pintype "bidirectional+no_connect"))
    )
    (net (code "51") (name "unconnected-(U4-PB5:OC1A:PCINT5-Pad41)") (class "Default")
      (node (ref "U4") (pin "41") (pinfunction "PB5:OC1A:PCINT5_41") (pintype "bidirectional+no_connect"))
    )
    (net (code "52") (name "unconnected-(U4-PB6:OC1B:PCINT6-Pad42)") (class "Default")
      (node (ref "U4") (pin "42") (pinfunction "PB6:OC1B:PCINT6_42") (pintype "bidirectional+no_connect"))
    )
    (net (code "53") (name "unconnected-(U4-PB7:OC0A:OC1C:PCINT7-Pad43)") (class "Default")
      (node (ref "U4") (pin "43") (pinfunction "PB7:OC0A:OC1C:PCINT7_43") (pintype "bidirectional+no_connect"))
    )
    (net (code "54") (name "unconnected-(U4-PD6:T1-Pad31)") (class "Default")
      (node (ref "U4") (pin "31") (pinfunction "PD6:T1_31") (pintype "bidirectional+no_connect"))
    )
    (net (code "55") (name "unconnected-(U4-PD7:T0-Pad32)") (class "Default")
      (node (ref "U4") (pin "32") (pinfunction "PD7:T0_32") (pintype "bidirectional+no_connect"))
    )
    (net (code "56") (name "unconnected-(U4-PE0:RXD0:PDI:PCINT8-Pad46)") (class "Default")
      (node (ref "U4") (pin "46") (pinfunction "PE0:RXD0:PDI:PCINT8_46") (pintype "bidirectional+no_connect"))
    )
    (net (code "57") (name "unconnected-(U4-PE1:TXD0:PDO-Pad47)") (class "Default")
      (node (ref "U4") (pin "47") (pinfunction "PE1:TXD0:PDO_47") (pintype "bidirectional+no_connect"))
    )
    (net (code "58") (name "unconnected-(U4-PE6:T3:INT6-Pad52)") (class "Default")
      (node (ref "U4") (pin "52") (pinfunction "PE6:T3:INT6_52") (pintype "bidirectional+no_connect"))
    )
    (net (code "59") (name "unconnected-(U4-PF3:ADC3:DIG4-Pad2)") (class "Default")
      (node (ref "U4") (pin "2") (pinfunction "PF3:ADC3:DIG4_2") (pintype "bidirectional+no_connect"))
    )
    (net (code "60") (name "unconnected-(U4-PG0:DIG3-Pad14)") (class "Default")
      (node (ref "U4") (pin "14") (pinfunction "PG0:DIG3_14") (pintype "bidirectional+no_connect"))
    )
    (net (code "61") (name "unconnected-(U4-PG1:DIG1-Pad15)") (class "Default")
      (node (ref "U4") (pin "15") (pinfunction "PG1:DIG1_15") (pintype "bidirectional+no_connect"))
    )
    (net (code "62") (name "unconnected-(U4-PG2_{slash}_AMR-Pad16)") (class "Default")
      (node (ref "U4") (pin "16") (pinfunction "PG2_/_AMR_16") (pintype "bidirectional+no_connect"))
    )
    (net (code "63") (name "unconnected-(U4-PG5:OC0B-Pad19)") (class "Default")
      (node (ref "U4") (pin "19") (pinfunction "PG5:OC0B_19") (pintype "bidirectional+no_connect"))
    )
    (net (code "64") (name "unconnected-(U4-RSTON-Pad13)") (class "Default")
      (node (ref "U4") (pin "13") (pinfunction "RSTON_13") (pintype "bidirectional+no_connect"))
    )
  )
)
